# RobotDriver.net
KiCad netlist of a schematic drawn in EAGLE
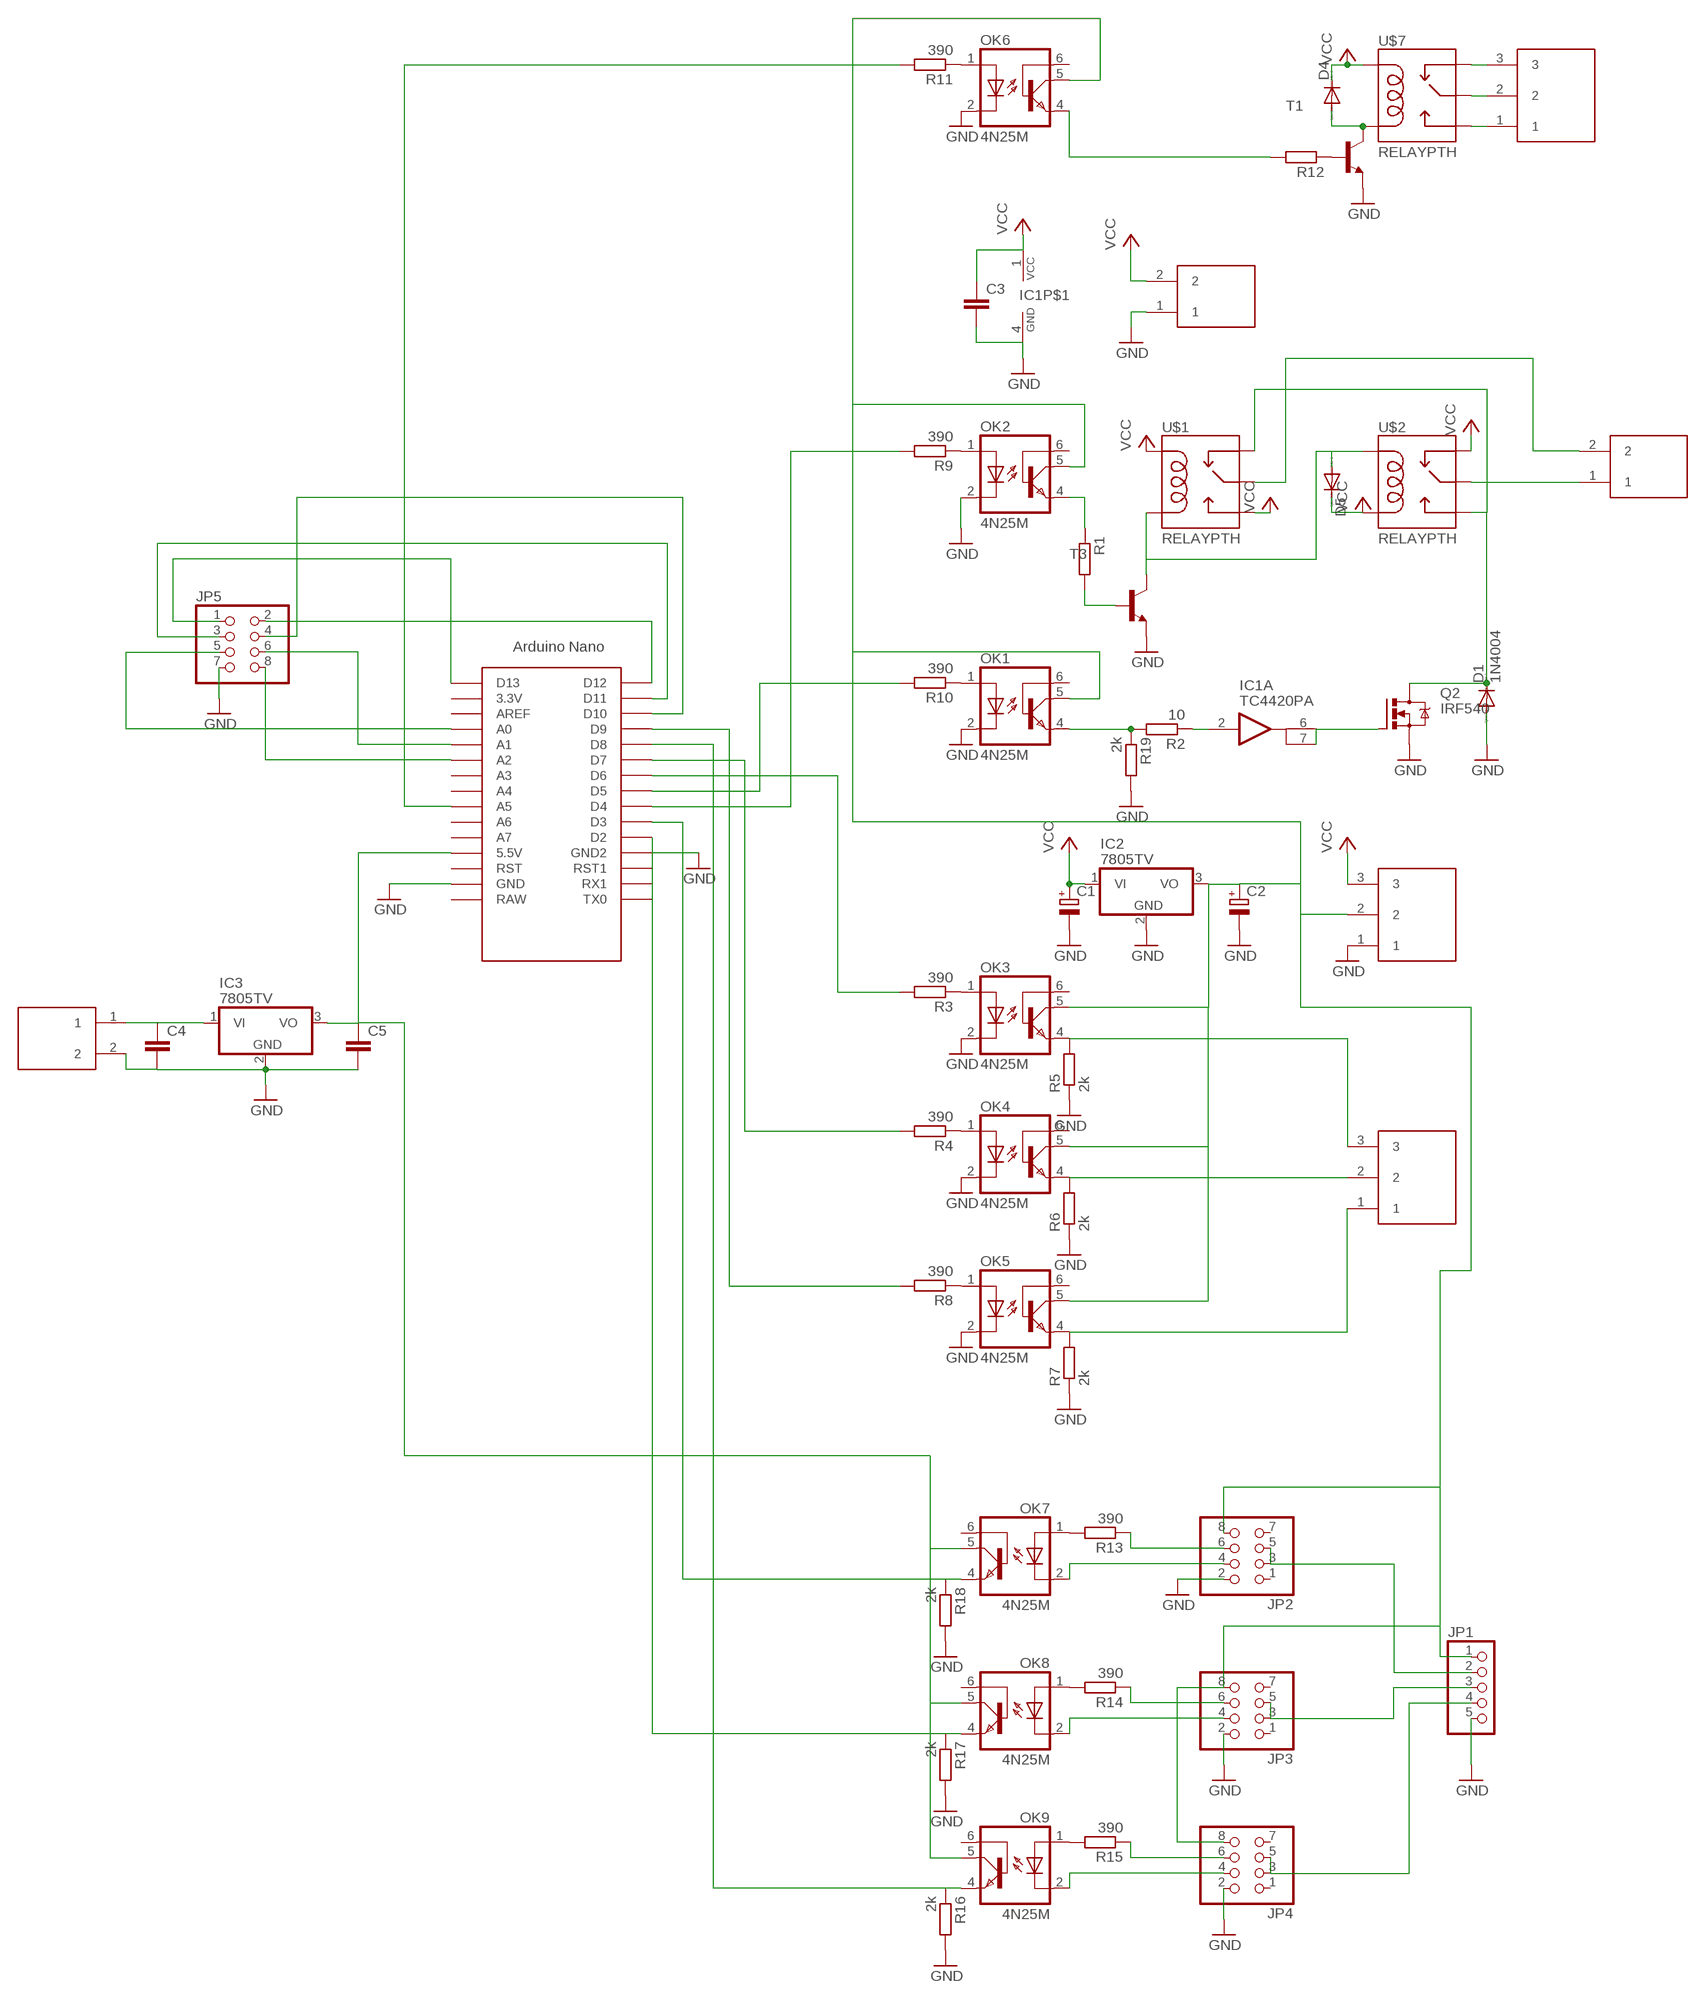
[diagram p0: schematic, sheet 1]

(export (version "E")
  (design (tool "Eeschema 10.0.6"))
  (components
    (comp (ref "C1")
      (value "CPOL-EUE5-10.5")
      (footprint "eagle-import:E5-10,5")
      (libsource (lib "eagle-import") (part "CPOL-EUE5-10.5"))
    )
    (comp (ref "C2")
      (value "CPOL-EUE5-10.5")
      (footprint "eagle-import:E5-10,5")
      (libsource (lib "eagle-import") (part "CPOL-EUE5-10.5"))
    )
    (comp (ref "C3")
      (value "C-EUC1206")
      (footprint "eagle-import:C1206")
      (libsource (lib "eagle-import") (part "C-EUC1206"))
    )
    (comp (ref "C4")
      (value "C-EUC1206")
      (footprint "eagle-import:C1206")
      (libsource (lib "eagle-import") (part "C-EUC1206"))
    )
    (comp (ref "C5")
      (value "C-EUC1206")
      (footprint "eagle-import:C1206")
      (libsource (lib "eagle-import") (part "C-EUC1206"))
    )
    (comp (ref "D1")
      (value "1N4004")
      (footprint "eagle-import:DO41-10")
      (libsource (lib "eagle-import") (part "1N4004"))
    )
    (comp (ref "D4")
      (value "DIODE-DO214AA")
      (footprint "eagle-import:DO214AA")
      (libsource (lib "eagle-import") (part "DIODE-DO214AA"))
    )
    (comp (ref "D5")
      (value "DIODE-DO214AA")
      (footprint "eagle-import:DO214AA")
      (libsource (lib "eagle-import") (part "DIODE-DO214AA"))
    )
    (comp (ref "IC1")
      (value "TC4420PA")
      (footprint "eagle-import:DIP08")
      (libsource (lib "eagle-import") (part "TC4420PA"))
    )
    (comp (ref "IC2")
      (value "7805TV")
      (footprint "eagle-import:TO220V")
      (libsource (lib "eagle-import") (part "78TV05"))
    )
    (comp (ref "IC3")
      (value "7805TV")
      (footprint "eagle-import:TO220V")
      (libsource (lib "eagle-import") (part "78TV05"))
    )
    (comp (ref "JP1")
      (value "PINHD-1X5")
      (footprint "eagle-import:1X05")
      (libsource (lib "eagle-import") (part "PINHD-1X5"))
    )
    (comp (ref "JP2")
      (value "PINHD-2X4")
      (footprint "eagle-import:2X04")
      (libsource (lib "eagle-import") (part "PINHD-2X4"))
    )
    (comp (ref "JP3")
      (value "PINHD-2X4")
      (footprint "eagle-import:2X04")
      (libsource (lib "eagle-import") (part "PINHD-2X4"))
    )
    (comp (ref "JP4")
      (value "PINHD-2X4")
      (footprint "eagle-import:2X04")
      (libsource (lib "eagle-import") (part "PINHD-2X4"))
    )
    (comp (ref "JP5")
      (value "PINHD-2X4")
      (footprint "eagle-import:2X04")
      (libsource (lib "eagle-import") (part "PINHD-2X4"))
    )
    (comp (ref "OK1")
      (value "4N25M")
      (footprint "eagle-import:DIL06")
      (fields (field (name "MPN") "4N25-M"))
      (libsource (lib "eagle-import") (part "4N?M25"))
    )
    (comp (ref "OK2")
      (value "4N25M")
      (footprint "eagle-import:DIL06")
      (fields (field (name "MPN") "4N25-M"))
      (libsource (lib "eagle-import") (part "4N?M25"))
    )
    (comp (ref "OK3")
      (value "4N25M")
      (footprint "eagle-import:DIL06")
      (fields (field (name "MPN") "4N25-M"))
      (libsource (lib "eagle-import") (part "4N?M25"))
    )
    (comp (ref "OK4")
      (value "4N25M")
      (footprint "eagle-import:DIL06")
      (fields (field (name "MPN") "4N25-M"))
      (libsource (lib "eagle-import") (part "4N?M25"))
    )
    (comp (ref "OK5")
      (value "4N25M")
      (footprint "eagle-import:DIL06")
      (fields (field (name "MPN") "4N25-M"))
      (libsource (lib "eagle-import") (part "4N?M25"))
    )
    (comp (ref "OK6")
      (value "4N25M")
      (footprint "eagle-import:DIL06")
      (fields (field (name "MPN") "4N25-M"))
      (libsource (lib "eagle-import") (part "4N?M25"))
    )
    (comp (ref "OK7")
      (value "4N25M")
      (footprint "eagle-import:DIL06")
      (fields (field (name "MPN") "4N25-M"))
      (libsource (lib "eagle-import") (part "4N?M25"))
    )
    (comp (ref "OK8")
      (value "4N25M")
      (footprint "eagle-import:DIL06")
      (fields (field (name "MPN") "4N25-M"))
      (libsource (lib "eagle-import") (part "4N?M25"))
    )
    (comp (ref "OK9")
      (value "4N25M")
      (footprint "eagle-import:DIL06")
      (fields (field (name "MPN") "4N25-M"))
      (libsource (lib "eagle-import") (part "4N?M25"))
    )
    (comp (ref "Q2")
      (value "IRF540")
      (footprint "eagle-import:TO220BV")
      (libsource (lib "eagle-import") (part "IRF540"))
    )
    (comp (ref "R1")
      (value "R-EU_R1210")
      (footprint "eagle-import:R1210")
      (libsource (lib "eagle-import") (part "R-EU_R1210"))
    )
    (comp (ref "R2")
      (value "10")
      (footprint "eagle-import:R1210")
      (libsource (lib "eagle-import") (part "R-EU_R1210"))
    )
    (comp (ref "R3")
      (value "390")
      (footprint "eagle-import:R1210")
      (libsource (lib "eagle-import") (part "R-EU_R1210"))
    )
    (comp (ref "R4")
      (value "390")
      (footprint "eagle-import:R1210")
      (libsource (lib "eagle-import") (part "R-EU_R1210"))
    )
    (comp (ref "R5")
      (value "2k")
      (footprint "eagle-import:R1210")
      (libsource (lib "eagle-import") (part "R-EU_R1210"))
    )
    (comp (ref "R6")
      (value "2k")
      (footprint "eagle-import:R1210")
      (libsource (lib "eagle-import") (part "R-EU_R1210"))
    )
    (comp (ref "R7")
      (value "2k")
      (footprint "eagle-import:R1210")
      (libsource (lib "eagle-import") (part "R-EU_R1210"))
    )
    (comp (ref "R8")
      (value "390")
      (footprint "eagle-import:R1210")
      (libsource (lib "eagle-import") (part "R-EU_R1210"))
    )
    (comp (ref "R9")
      (value "390")
      (footprint "eagle-import:R1210")
      (libsource (lib "eagle-import") (part "R-EU_R1210"))
    )
    (comp (ref "R10")
      (value "390")
      (footprint "eagle-import:R1210")
      (libsource (lib "eagle-import") (part "R-EU_R1210"))
    )
    (comp (ref "R11")
      (value "390")
      (footprint "eagle-import:R1210")
      (libsource (lib "eagle-import") (part "R-EU_R1210"))
    )
    (comp (ref "R12")
      (value "R-EU_R1210")
      (footprint "eagle-import:R1210")
      (libsource (lib "eagle-import") (part "R-EU_R1210"))
    )
    (comp (ref "R13")
      (value "390")
      (footprint "eagle-import:R1210")
      (libsource (lib "eagle-import") (part "R-EU_R1210"))
    )
    (comp (ref "R14")
      (value "390")
      (footprint "eagle-import:R1210")
      (libsource (lib "eagle-import") (part "R-EU_R1210"))
    )
    (comp (ref "R15")
      (value "390")
      (footprint "eagle-import:R1210")
      (libsource (lib "eagle-import") (part "R-EU_R1210"))
    )
    (comp (ref "R16")
      (value "2k")
      (footprint "eagle-import:R1210")
      (libsource (lib "eagle-import") (part "R-EU_R1210"))
    )
    (comp (ref "R17")
      (value "2k")
      (footprint "eagle-import:R1210")
      (libsource (lib "eagle-import") (part "R-EU_R1210"))
    )
    (comp (ref "R18")
      (value "2k")
      (footprint "eagle-import:R1210")
      (libsource (lib "eagle-import") (part "R-EU_R1210"))
    )
    (comp (ref "R19")
      (value "2k")
      (footprint "eagle-import:R1210")
      (libsource (lib "eagle-import") (part "R-EU_R1210"))
    )
    (comp (ref "T1")
      (value "BC817-16-NPN-SOT23-BEC")
      (footprint "eagle-import:SOT23-BEC")
      (libsource (lib "eagle-import") (part "-NPN-SOT23-BECBC817-16"))
    )
    (comp (ref "T3")
      (value "BC817-16-NPN-SOT23-BEC")
      (footprint "eagle-import:SOT23-BEC")
      (libsource (lib "eagle-import") (part "-NPN-SOT23-BECBC817-16"))
    )
    (comp (ref "U$1")
      (value "RELAYPTH")
      (footprint "eagle-import:SRD-05VDC-SL-C")
      (libsource (lib "eagle-import") (part "RELAYPTH"))
    )
    (comp (ref "U$2")
      (value "RELAYPTH")
      (footprint "eagle-import:SRD-05VDC-SL-C")
      (libsource (lib "eagle-import") (part "RELAYPTH"))
    )
    (comp (ref "U$3")
      (value "NANO")
      (footprint "eagle-import:NANO")
      (libsource (lib "eagle-import") (part "NANO"))
    )
    (comp (ref "U$4")
      (value "2EDG-2")
      (footprint "eagle-import:2EGD-2-PAK")
      (libsource (lib "eagle-import") (part "2EDG-2"))
    )
    (comp (ref "U$5")
      (value "2EDG-2")
      (footprint "eagle-import:2EGD-2-PAK")
      (libsource (lib "eagle-import") (part "2EDG-2"))
    )
    (comp (ref "U$6")
      (value "2EDG-3")
      (footprint "eagle-import:2EGD-3-PAK")
      (libsource (lib "eagle-import") (part "2EDG-3"))
    )
    (comp (ref "U$7")
      (value "RELAYPTH")
      (footprint "eagle-import:SRD-05VDC-SL-C")
      (libsource (lib "eagle-import") (part "RELAYPTH"))
    )
    (comp (ref "U$8")
      (value "2EDG-3")
      (footprint "eagle-import:2EGD-3-PAK")
      (libsource (lib "eagle-import") (part "2EDG-3"))
    )
    (comp (ref "U$9")
      (value "2EDG-3")
      (footprint "eagle-import:2EGD-3-PAK")
      (libsource (lib "eagle-import") (part "2EDG-3"))
    )
    (comp (ref "U$10")
      (value "2EDG-2")
      (footprint "eagle-import:2EGD-2-PAK")
      (libsource (lib "eagle-import") (part "2EDG-2"))
    )
  )
  (nets
    (net (code "1") (name "GND") (class "Default")
      (node (ref "C1") (pin "-") (pinfunction "-_-") (pintype "passive"))
      (node (ref "C2") (pin "-") (pinfunction "-_-") (pintype "passive"))
      (node (ref "C3") (pin "2") (pinfunction "2_2") (pintype "passive"))
      (node (ref "C4") (pin "2") (pinfunction "2_2") (pintype "passive"))
      (node (ref "C5") (pin "2") (pinfunction "2_2") (pintype "passive"))
      (node (ref "D1") (pin "A") (pinfunction "A_A") (pintype "passive"))
      (node (ref "IC1") (pin "4") (pinfunction "GND_4") (pintype "power_in"))
      (node (ref "IC2") (pin "2") (pinfunction "GND_2") (pintype "passive"))
      (node (ref "IC3") (pin "2") (pinfunction "GND_2") (pintype "passive"))
      (node (ref "JP1") (pin "5") (pinfunction "5_5") (pintype "passive"))
      (node (ref "JP2") (pin "2") (pinfunction "2_2") (pintype "passive"))
      (node (ref "JP3") (pin "2") (pinfunction "2_2") (pintype "passive"))
      (node (ref "JP4") (pin "2") (pinfunction "2_2") (pintype "passive"))
      (node (ref "JP5") (pin "7") (pinfunction "7_7") (pintype "passive"))
      (node (ref "OK1") (pin "2") (pinfunction "C_2") (pintype "passive"))
      (node (ref "OK2") (pin "2") (pinfunction "C_2") (pintype "passive"))
      (node (ref "OK3") (pin "2") (pinfunction "C_2") (pintype "passive"))
      (node (ref "OK4") (pin "2") (pinfunction "C_2") (pintype "passive"))
      (node (ref "OK5") (pin "2") (pinfunction "C_2") (pintype "passive"))
      (node (ref "OK6") (pin "2") (pinfunction "C_2") (pintype "passive"))
      (node (ref "Q2") (pin "S") (pinfunction "S_S") (pintype "passive"))
      (node (ref "R16") (pin "2") (pinfunction "2_2") (pintype "passive"))
      (node (ref "R17") (pin "2") (pinfunction "2_2") (pintype "passive"))
      (node (ref "R18") (pin "2") (pinfunction "2_2") (pintype "passive"))
      (node (ref "R19") (pin "2") (pinfunction "2_2") (pintype "passive"))
      (node (ref "R5") (pin "1") (pinfunction "1_1") (pintype "passive"))
      (node (ref "R6") (pin "1") (pinfunction "1_1") (pintype "passive"))
      (node (ref "R7") (pin "1") (pinfunction "1_1") (pintype "passive"))
      (node (ref "T1") (pin "E") (pinfunction "E_E") (pintype "passive"))
      (node (ref "T3") (pin "E") (pinfunction "E_E") (pintype "passive"))
      (node (ref "U$10") (pin "2") (pinfunction "2_2") (pintype "bidirectional"))
      (node (ref "U$3") (pin "GND") (pinfunction "GND_GND") (pintype "bidirectional"))
      (node (ref "U$3") (pin "GND1") (pinfunction "GND2_GND1") (pintype "bidirectional"))
      (node (ref "U$5") (pin "1") (pinfunction "1_1") (pintype "bidirectional"))
      (node (ref "U$9") (pin "1") (pinfunction "1_1") (pintype "bidirectional"))
    )
    (net (code "2") (name "Net-(D4-PadA)") (class "Default")
      (node (ref "D4") (pin "A") (pinfunction "A_A") (pintype "passive"))
      (node (ref "T1") (pin "C") (pinfunction "C_C") (pintype "passive"))
      (node (ref "U$7") (pin "COIL0") (pinfunction "COIL0_COIL0") (pintype "bidirectional"))
    )
    (net (code "3") (name "Net-(D5-PadA)") (class "Default")
      (node (ref "D5") (pin "A") (pinfunction "A_A") (pintype "passive"))
      (node (ref "T3") (pin "C") (pinfunction "C_C") (pintype "passive"))
      (node (ref "U$1") (pin "COIL0") (pinfunction "COIL0_COIL0") (pintype "bidirectional"))
      (node (ref "U$2") (pin "COIL1") (pinfunction "COIL1_COIL1") (pintype "bidirectional"))
    )
    (net (code "4") (name "Net-(IC1A-IN)") (class "Default")
      (node (ref "IC1") (pin "2") (pinfunction "IN_2") (pintype "input"))
      (node (ref "R2") (pin "1") (pinfunction "1_1") (pintype "passive"))
    )
    (net (code "5") (name "Net-(IC1A-OUT1)") (class "Default")
      (node (ref "IC1") (pin "6") (pinfunction "OUT1_6") (pintype "output"))
      (node (ref "IC1") (pin "7") (pinfunction "OUT2_7") (pintype "output"))
      (node (ref "Q2") (pin "G") (pinfunction "G_G") (pintype "passive"))
    )
    (net (code "6") (name "Net-(IC2-VO)") (class "Default")
      (node (ref "C2") (pin "+") (pinfunction "+_+") (pintype "passive"))
      (node (ref "IC2") (pin "3") (pinfunction "VO_3") (pintype "passive"))
      (node (ref "JP1") (pin "1") (pinfunction "1_1") (pintype "passive"))
      (node (ref "JP2") (pin "8") (pinfunction "8_8") (pintype "passive"))
      (node (ref "JP3") (pin "8") (pinfunction "8_8") (pintype "passive"))
      (node (ref "JP4") (pin "8") (pinfunction "8_8") (pintype "passive"))
      (node (ref "OK1") (pin "5") (pinfunction "COL_5") (pintype "passive"))
      (node (ref "OK2") (pin "5") (pinfunction "COL_5") (pintype "passive"))
      (node (ref "OK3") (pin "5") (pinfunction "COL_5") (pintype "passive"))
      (node (ref "OK4") (pin "5") (pinfunction "COL_5") (pintype "passive"))
      (node (ref "OK5") (pin "5") (pinfunction "COL_5") (pintype "passive"))
      (node (ref "OK6") (pin "5") (pinfunction "COL_5") (pintype "passive"))
      (node (ref "U$9") (pin "2") (pinfunction "2_2") (pintype "bidirectional"))
    )
    (net (code "7") (name "Net-(IC3-VI)") (class "Default")
      (node (ref "C4") (pin "1") (pinfunction "1_1") (pintype "passive"))
      (node (ref "IC3") (pin "1") (pinfunction "VI_1") (pintype "input"))
      (node (ref "U$10") (pin "1") (pinfunction "1_1") (pintype "bidirectional"))
    )
    (net (code "8") (name "Net-(IC3-VO)") (class "Default")
      (node (ref "C5") (pin "1") (pinfunction "1_1") (pintype "passive"))
      (node (ref "IC3") (pin "3") (pinfunction "VO_3") (pintype "passive"))
      (node (ref "OK7") (pin "5") (pinfunction "COL_5") (pintype "passive"))
      (node (ref "OK8") (pin "5") (pinfunction "COL_5") (pintype "passive"))
      (node (ref "OK9") (pin "5") (pinfunction "COL_5") (pintype "passive"))
      (node (ref "U$3") (pin "5V") (pinfunction "5.5V_5V") (pintype "bidirectional"))
    )
    (net (code "9") (name "Net-(JP1-Pad2)") (class "Default")
      (node (ref "JP1") (pin "2") (pinfunction "2_2") (pintype "passive"))
      (node (ref "JP2") (pin "3") (pinfunction "3_3") (pintype "passive"))
      (node (ref "JP2") (pin "5") (pinfunction "5_5") (pintype "passive"))
    )
    (net (code "10") (name "Net-(JP1-Pad3)") (class "Default")
      (node (ref "JP1") (pin "3") (pinfunction "3_3") (pintype "passive"))
      (node (ref "JP3") (pin "3") (pinfunction "3_3") (pintype "passive"))
      (node (ref "JP3") (pin "5") (pinfunction "5_5") (pintype "passive"))
    )
    (net (code "11") (name "Net-(JP1-Pad4)") (class "Default")
      (node (ref "JP1") (pin "4") (pinfunction "4_4") (pintype "passive"))
      (node (ref "JP4") (pin "3") (pinfunction "3_3") (pintype "passive"))
      (node (ref "JP4") (pin "5") (pinfunction "5_5") (pintype "passive"))
    )
    (net (code "12") (name "Net-(JP2-Pad6)") (class "Default")
      (node (ref "JP2") (pin "6") (pinfunction "6_6") (pintype "passive"))
      (node (ref "R13") (pin "1") (pinfunction "1_1") (pintype "passive"))
    )
    (net (code "13") (name "Net-(JP3-Pad6)") (class "Default")
      (node (ref "JP3") (pin "6") (pinfunction "6_6") (pintype "passive"))
      (node (ref "R14") (pin "1") (pinfunction "1_1") (pintype "passive"))
    )
    (net (code "14") (name "Net-(JP4-Pad6)") (class "Default")
      (node (ref "JP4") (pin "6") (pinfunction "6_6") (pintype "passive"))
      (node (ref "R15") (pin "1") (pinfunction "1_1") (pintype "passive"))
    )
    (net (code "15") (name "Net-(JP5-Pad1)") (class "Default")
      (node (ref "JP5") (pin "1") (pinfunction "1_1") (pintype "passive"))
      (node (ref "U$3") (pin "D13") (pinfunction "D13_D13") (pintype "bidirectional"))
    )
    (net (code "16") (name "Net-(JP5-Pad2)") (class "Default")
      (node (ref "JP5") (pin "2") (pinfunction "2_2") (pintype "passive"))
      (node (ref "U$3") (pin "D12") (pinfunction "D12_D12") (pintype "bidirectional"))
    )
    (net (code "17") (name "Net-(JP5-Pad3)") (class "Default")
      (node (ref "JP5") (pin "3") (pinfunction "3_3") (pintype "passive"))
      (node (ref "U$3") (pin "D11") (pinfunction "D11_D11") (pintype "bidirectional"))
    )
    (net (code "18") (name "Net-(JP5-Pad4)") (class "Default")
      (node (ref "JP5") (pin "4") (pinfunction "4_4") (pintype "passive"))
      (node (ref "U$3") (pin "D10") (pinfunction "D10_D10") (pintype "bidirectional"))
    )
    (net (code "19") (name "Net-(JP5-Pad5)") (class "Default")
      (node (ref "JP5") (pin "5") (pinfunction "5_5") (pintype "passive"))
      (node (ref "U$3") (pin "A0") (pinfunction "A0_A0") (pintype "bidirectional"))
    )
    (net (code "20") (name "Net-(JP5-Pad6)") (class "Default")
      (node (ref "JP5") (pin "6") (pinfunction "6_6") (pintype "passive"))
      (node (ref "U$3") (pin "A1") (pinfunction "A1_A1") (pintype "bidirectional"))
    )
    (net (code "21") (name "Net-(JP5-Pad8)") (class "Default")
      (node (ref "JP5") (pin "8") (pinfunction "8_8") (pintype "passive"))
      (node (ref "U$3") (pin "A2") (pinfunction "A2_A2") (pintype "bidirectional"))
    )
    (net (code "22") (name "Net-(OK1-A)") (class "Default")
      (node (ref "OK1") (pin "1") (pinfunction "A_1") (pintype "passive"))
      (node (ref "R10") (pin "1") (pinfunction "1_1") (pintype "passive"))
    )
    (net (code "23") (name "Net-(OK1-EMI)") (class "Default")
      (node (ref "OK1") (pin "4") (pinfunction "EMI_4") (pintype "passive"))
      (node (ref "R19") (pin "1") (pinfunction "1_1") (pintype "passive"))
      (node (ref "R2") (pin "2") (pinfunction "2_2") (pintype "passive"))
    )
    (net (code "24") (name "Net-(OK2-A)") (class "Default")
      (node (ref "OK2") (pin "1") (pinfunction "A_1") (pintype "passive"))
      (node (ref "R9") (pin "1") (pinfunction "1_1") (pintype "passive"))
    )
    (net (code "25") (name "Net-(OK2-EMI)") (class "Default")
      (node (ref "OK2") (pin "4") (pinfunction "EMI_4") (pintype "passive"))
      (node (ref "R1") (pin "1") (pinfunction "1_1") (pintype "passive"))
    )
    (net (code "26") (name "Net-(OK3-A)") (class "Default")
      (node (ref "OK3") (pin "1") (pinfunction "A_1") (pintype "passive"))
      (node (ref "R3") (pin "1") (pinfunction "1_1") (pintype "passive"))
    )
    (net (code "27") (name "Net-(OK3-EMI)") (class "Default")
      (node (ref "OK3") (pin "4") (pinfunction "EMI_4") (pintype "passive"))
      (node (ref "R5") (pin "2") (pinfunction "2_2") (pintype "passive"))
      (node (ref "U$6") (pin "3") (pinfunction "3_3") (pintype "bidirectional"))
    )
    (net (code "28") (name "Net-(OK4-A)") (class "Default")
      (node (ref "OK4") (pin "1") (pinfunction "A_1") (pintype "passive"))
      (node (ref "R4") (pin "1") (pinfunction "1_1") (pintype "passive"))
    )
    (net (code "29") (name "Net-(OK4-EMI)") (class "Default")
      (node (ref "OK4") (pin "4") (pinfunction "EMI_4") (pintype "passive"))
      (node (ref "R6") (pin "2") (pinfunction "2_2") (pintype "passive"))
      (node (ref "U$6") (pin "2") (pinfunction "2_2") (pintype "bidirectional"))
    )
    (net (code "30") (name "Net-(OK5-A)") (class "Default")
      (node (ref "OK5") (pin "1") (pinfunction "A_1") (pintype "passive"))
      (node (ref "R8") (pin "1") (pinfunction "1_1") (pintype "passive"))
    )
    (net (code "31") (name "Net-(OK5-EMI)") (class "Default")
      (node (ref "OK5") (pin "4") (pinfunction "EMI_4") (pintype "passive"))
      (node (ref "R7") (pin "2") (pinfunction "2_2") (pintype "passive"))
      (node (ref "U$6") (pin "1") (pinfunction "1_1") (pintype "bidirectional"))
    )
    (net (code "32") (name "Net-(OK6-A)") (class "Default")
      (node (ref "OK6") (pin "1") (pinfunction "A_1") (pintype "passive"))
      (node (ref "R11") (pin "1") (pinfunction "1_1") (pintype "passive"))
    )
    (net (code "33") (name "Net-(OK6-EMI)") (class "Default")
      (node (ref "OK6") (pin "4") (pinfunction "EMI_4") (pintype "passive"))
      (node (ref "R12") (pin "2") (pinfunction "2_2") (pintype "passive"))
    )
    (net (code "34") (name "Net-(OK7-A)") (class "Default")
      (node (ref "OK7") (pin "1") (pinfunction "A_1") (pintype "passive"))
      (node (ref "R13") (pin "2") (pinfunction "2_2") (pintype "passive"))
    )
    (net (code "35") (name "Net-(OK7-C)") (class "Default")
      (node (ref "JP2") (pin "4") (pinfunction "4_4") (pintype "passive"))
      (node (ref "OK7") (pin "2") (pinfunction "C_2") (pintype "passive"))
    )
    (net (code "36") (name "Net-(OK7-EMI)") (class "Default")
      (node (ref "OK7") (pin "4") (pinfunction "EMI_4") (pintype "passive"))
      (node (ref "R18") (pin "1") (pinfunction "1_1") (pintype "passive"))
      (node (ref "U$3") (pin "D3") (pinfunction "D3_D3") (pintype "bidirectional"))
    )
    (net (code "37") (name "Net-(OK8-A)") (class "Default")
      (node (ref "OK8") (pin "1") (pinfunction "A_1") (pintype "passive"))
      (node (ref "R14") (pin "2") (pinfunction "2_2") (pintype "passive"))
    )
    (net (code "38") (name "Net-(OK8-C)") (class "Default")
      (node (ref "JP3") (pin "4") (pinfunction "4_4") (pintype "passive"))
      (node (ref "OK8") (pin "2") (pinfunction "C_2") (pintype "passive"))
    )
    (net (code "39") (name "Net-(OK8-EMI)") (class "Default")
      (node (ref "OK8") (pin "4") (pinfunction "EMI_4") (pintype "passive"))
      (node (ref "R17") (pin "1") (pinfunction "1_1") (pintype "passive"))
      (node (ref "U$3") (pin "D2") (pinfunction "D2_D2") (pintype "bidirectional"))
    )
    (net (code "40") (name "Net-(OK9-A)") (class "Default")
      (node (ref "OK9") (pin "1") (pinfunction "A_1") (pintype "passive"))
      (node (ref "R15") (pin "2") (pinfunction "2_2") (pintype "passive"))
    )
    (net (code "41") (name "Net-(OK9-C)") (class "Default")
      (node (ref "JP4") (pin "4") (pinfunction "4_4") (pintype "passive"))
      (node (ref "OK9") (pin "2") (pinfunction "C_2") (pintype "passive"))
    )
    (net (code "42") (name "Net-(OK9-EMI)") (class "Default")
      (node (ref "OK9") (pin "4") (pinfunction "EMI_4") (pintype "passive"))
      (node (ref "R16") (pin "1") (pinfunction "1_1") (pintype "passive"))
      (node (ref "U$3") (pin "D8") (pinfunction "D8_D8") (pintype "bidirectional"))
    )
    (net (code "43") (name "Net-(R1-Pad2)") (class "Default")
      (node (ref "R1") (pin "2") (pinfunction "2_2") (pintype "passive"))
      (node (ref "T3") (pin "B") (pinfunction "B_B") (pintype "passive"))
    )
    (net (code "44") (name "Net-(R3-Pad2)") (class "Default")
      (node (ref "R3") (pin "2") (pinfunction "2_2") (pintype "passive"))
      (node (ref "U$3") (pin "D6") (pinfunction "D6_D6") (pintype "bidirectional"))
    )
    (net (code "45") (name "Net-(R4-Pad2)") (class "Default")
      (node (ref "R4") (pin "2") (pinfunction "2_2") (pintype "passive"))
      (node (ref "U$3") (pin "D7") (pinfunction "D7_D7") (pintype "bidirectional"))
    )
    (net (code "46") (name "Net-(R8-Pad2)") (class "Default")
      (node (ref "R8") (pin "2") (pinfunction "2_2") (pintype "passive"))
      (node (ref "U$3") (pin "D9") (pinfunction "D9_D9") (pintype "bidirectional"))
    )
    (net (code "47") (name "Net-(R9-Pad2)") (class "Default")
      (node (ref "R9") (pin "2") (pinfunction "2_2") (pintype "passive"))
      (node (ref "U$3") (pin "D4") (pinfunction "D4_D4") (pintype "bidirectional"))
    )
    (net (code "48") (name "Net-(R10-Pad2)") (class "Default")
      (node (ref "R10") (pin "2") (pinfunction "2_2") (pintype "passive"))
      (node (ref "U$3") (pin "D5") (pinfunction "D5_D5") (pintype "bidirectional"))
    )
    (net (code "49") (name "Net-(R11-Pad2)") (class "Default")
      (node (ref "R11") (pin "2") (pinfunction "2_2") (pintype "passive"))
      (node (ref "U$3") (pin "A5") (pinfunction "A5_A5") (pintype "bidirectional"))
    )
    (net (code "50") (name "Net-(R12-Pad1)") (class "Default")
      (node (ref "R12") (pin "1") (pinfunction "1_1") (pintype "passive"))
      (node (ref "T1") (pin "B") (pinfunction "B_B") (pintype "passive"))
    )
    (net (code "51") (name "Net-(U$1-PadSWCOMMON)") (class "Default")
      (node (ref "U$1") (pin "SWCOMMON") (pinfunction "SWCOMMON_SWCOMMON") (pintype "bidirectional"))
      (node (ref "U$4") (pin "2") (pinfunction "2_2") (pintype "bidirectional"))
    )
    (net (code "52") (name "Net-(U$1-SWCLOSE)") (class "Default")
      (node (ref "D1") (pin "C") (pinfunction "C_C") (pintype "passive"))
      (node (ref "Q2") (pin "D") (pinfunction "D_D") (pintype "passive"))
      (node (ref "U$1") (pin "SWCLOSED") (pinfunction "SWCLOSE_SWCLOSED") (pintype "bidirectional"))
      (node (ref "U$2") (pin "SWOPEN") (pinfunction "SWOPEN_SWOPEN") (pintype "bidirectional"))
    )
    (net (code "53") (name "Net-(U$2-PadSWCOMMON)") (class "Default")
      (node (ref "U$2") (pin "SWCOMMON") (pinfunction "SWCOMMON_SWCOMMON") (pintype "bidirectional"))
      (node (ref "U$4") (pin "1") (pinfunction "1_1") (pintype "bidirectional"))
    )
    (net (code "54") (name "Net-(U$7-PadSWCOMMON)") (class "Default")
      (node (ref "U$7") (pin "SWCOMMON") (pinfunction "SWCOMMON_SWCOMMON") (pintype "bidirectional"))
      (node (ref "U$8") (pin "2") (pinfunction "2_2") (pintype "bidirectional"))
    )
    (net (code "55") (name "Net-(U$7-PadSWOPEN)") (class "Default")
      (node (ref "U$7") (pin "SWOPEN") (pinfunction "SWOPEN_SWOPEN") (pintype "bidirectional"))
      (node (ref "U$8") (pin "1") (pinfunction "1_1") (pintype "bidirectional"))
    )
    (net (code "56") (name "Net-(U$7-SWCLOSE)") (class "Default")
      (node (ref "U$7") (pin "SWCLOSED") (pinfunction "SWCLOSE_SWCLOSED") (pintype "bidirectional"))
      (node (ref "U$8") (pin "3") (pinfunction "3_3") (pintype "bidirectional"))
    )
    (net (code "57") (name "VCC") (class "Default")
      (node (ref "C1") (pin "+") (pinfunction "+_+") (pintype "passive"))
      (node (ref "C3") (pin "1") (pinfunction "1_1") (pintype "passive"))
      (node (ref "D4") (pin "C") (pinfunction "C_C") (pintype "passive"))
      (node (ref "D5") (pin "C") (pinfunction "C_C") (pintype "passive"))
      (node (ref "IC1") (pin "1") (pinfunction "VCC_1") (pintype "power_in"))
      (node (ref "IC2") (pin "1") (pinfunction "VI_1") (pintype "input"))
      (node (ref "U$1") (pin "COIL1") (pinfunction "COIL1_COIL1") (pintype "bidirectional"))
      (node (ref "U$1") (pin "SWOPEN") (pinfunction "SWOPEN_SWOPEN") (pintype "bidirectional"))
      (node (ref "U$2") (pin "COIL0") (pinfunction "COIL0_COIL0") (pintype "bidirectional"))
      (node (ref "U$2") (pin "SWCLOSED") (pinfunction "SWCLOSE_SWCLOSED") (pintype "bidirectional"))
      (node (ref "U$5") (pin "2") (pinfunction "2_2") (pintype "bidirectional"))
      (node (ref "U$7") (pin "COIL1") (pinfunction "COIL1_COIL1") (pintype "bidirectional"))
      (node (ref "U$9") (pin "3") (pinfunction "3_3") (pintype "bidirectional"))
    )
    (net (code "58") (name "unconnected-(JP2-Pad1)") (class "Default")
      (node (ref "JP2") (pin "1") (pinfunction "1_1") (pintype "passive"))
    )
    (net (code "59") (name "unconnected-(JP2-Pad7)") (class "Default")
      (node (ref "JP2") (pin "7") (pinfunction "7_7") (pintype "passive"))
    )
    (net (code "60") (name "unconnected-(JP3-Pad1)") (class "Default")
      (node (ref "JP3") (pin "1") (pinfunction "1_1") (pintype "passive"))
    )
    (net (code "61") (name "unconnected-(JP3-Pad7)") (class "Default")
      (node (ref "JP3") (pin "7") (pinfunction "7_7") (pintype "passive"))
    )
    (net (code "62") (name "unconnected-(JP4-Pad1)") (class "Default")
      (node (ref "JP4") (pin "1") (pinfunction "1_1") (pintype "passive"))
    )
    (net (code "63") (name "unconnected-(JP4-Pad7)") (class "Default")
      (node (ref "JP4") (pin "7") (pinfunction "7_7") (pintype "passive"))
    )
    (net (code "64") (name "unconnected-(OK1-BAS-Pad6)") (class "Default")
      (node (ref "OK1") (pin "6") (pinfunction "BAS_6") (pintype "passive"))
    )
    (net (code "65") (name "unconnected-(OK2-BAS-Pad6)") (class "Default")
      (node (ref "OK2") (pin "6") (pinfunction "BAS_6") (pintype "passive"))
    )
    (net (code "66") (name "unconnected-(OK3-BAS-Pad6)") (class "Default")
      (node (ref "OK3") (pin "6") (pinfunction "BAS_6") (pintype "passive"))
    )
    (net (code "67") (name "unconnected-(OK4-BAS-Pad6)") (class "Default")
      (node (ref "OK4") (pin "6") (pinfunction "BAS_6") (pintype "passive"))
    )
    (net (code "68") (name "unconnected-(OK5-BAS-Pad6)") (class "Default")
      (node (ref "OK5") (pin "6") (pinfunction "BAS_6") (pintype "passive"))
    )
    (net (code "69") (name "unconnected-(OK6-BAS-Pad6)") (class "Default")
      (node (ref "OK6") (pin "6") (pinfunction "BAS_6") (pintype "passive"))
    )
    (net (code "70") (name "unconnected-(OK7-BAS-Pad6)") (class "Default")
      (node (ref "OK7") (pin "6") (pinfunction "BAS_6") (pintype "passive"))
    )
    (net (code "71") (name "unconnected-(OK8-BAS-Pad6)") (class "Default")
      (node (ref "OK8") (pin "6") (pinfunction "BAS_6") (pintype "passive"))
    )
    (net (code "72") (name "unconnected-(OK9-BAS-Pad6)") (class "Default")
      (node (ref "OK9") (pin "6") (pinfunction "BAS_6") (pintype "passive"))
    )
    (net (code "73") (name "unconnected-(U$3-Pad3.3V)") (class "Default")
      (node (ref "U$3") (pin "3.3V") (pinfunction "3.3V_3.3V") (pintype "bidirectional"))
    )
    (net (code "74") (name "unconnected-(U$3-PadA3)") (class "Default")
      (node (ref "U$3") (pin "A3") (pinfunction "A3_A3") (pintype "bidirectional"))
    )
    (net (code "75") (name "unconnected-(U$3-PadA4)") (class "Default")
      (node (ref "U$3") (pin "A4") (pinfunction "A4_A4") (pintype "bidirectional"))
    )
    (net (code "76") (name "unconnected-(U$3-PadA6)") (class "Default")
      (node (ref "U$3") (pin "A6") (pinfunction "A6_A6") (pintype "bidirectional"))
    )
    (net (code "77") (name "unconnected-(U$3-PadA7)") (class "Default")
      (node (ref "U$3") (pin "A7") (pinfunction "A7_A7") (pintype "bidirectional"))
    )
    (net (code "78") (name "unconnected-(U$3-PadAREF)") (class "Default")
      (node (ref "U$3") (pin "AREF") (pinfunction "AREF_AREF") (pintype "bidirectional"))
    )
    (net (code "79") (name "unconnected-(U$3-PadICSP1)") (class "Default")
      (node (ref "U$3") (pin "ICSP1") (pinfunction "ICSP1_ICSP1") (pintype "bidirectional"))
    )
    (net (code "80") (name "unconnected-(U$3-PadICSP2)") (class "Default")
      (node (ref "U$3") (pin "ICSP2") (pinfunction "ICSP2_ICSP2") (pintype "bidirectional"))
    )
    (net (code "81") (name "unconnected-(U$3-PadICSP3)") (class "Default")
      (node (ref "U$3") (pin "ICSP3") (pinfunction "ICSP3_ICSP3") (pintype "bidirectional"))
    )
    (net (code "82") (name "unconnected-(U$3-PadICSP4)") (class "Default")
      (node (ref "U$3") (pin "ICSP4") (pinfunction "ICSP4_ICSP4") (pintype "bidirectional"))
    )
    (net (code "83") (name "unconnected-(U$3-PadICSP5)") (class "Default")
      (node (ref "U$3") (pin "ICSP5") (pinfunction "ICSP5_ICSP5") (pintype "bidirectional"))
    )
    (net (code "84") (name "unconnected-(U$3-PadICSP6)") (class "Default")
      (node (ref "U$3") (pin "ICSP6") (pinfunction "ICSP6_ICSP6") (pintype "bidirectional"))
    )
    (net (code "85") (name "unconnected-(U$3-PadRAW)") (class "Default")
      (node (ref "U$3") (pin "RAW") (pinfunction "RAW_RAW") (pintype "bidirectional"))
    )
    (net (code "86") (name "unconnected-(U$3-PadRST)") (class "Default")
      (node (ref "U$3") (pin "RST") (pinfunction "RST_RST") (pintype "bidirectional"))
    )
    (net (code "87") (name "unconnected-(U$3-PadRST1)") (class "Default")
      (node (ref "U$3") (pin "RST1") (pinfunction "RST1_RST1") (pintype "bidirectional"))
    )
    (net (code "88") (name "unconnected-(U$3-PadRX1)") (class "Default")
      (node (ref "U$3") (pin "RX1") (pinfunction "RX1_RX1") (pintype "bidirectional"))
    )
    (net (code "89") (name "unconnected-(U$3-PadTX0)") (class "Default")
      (node (ref "U$3") (pin "TX0") (pinfunction "TX0_TX0") (pintype "bidirectional"))
    )
  )
)
